# USBtoEthnet.net
KiCad netlist of a schematic drawn in Altium Designer
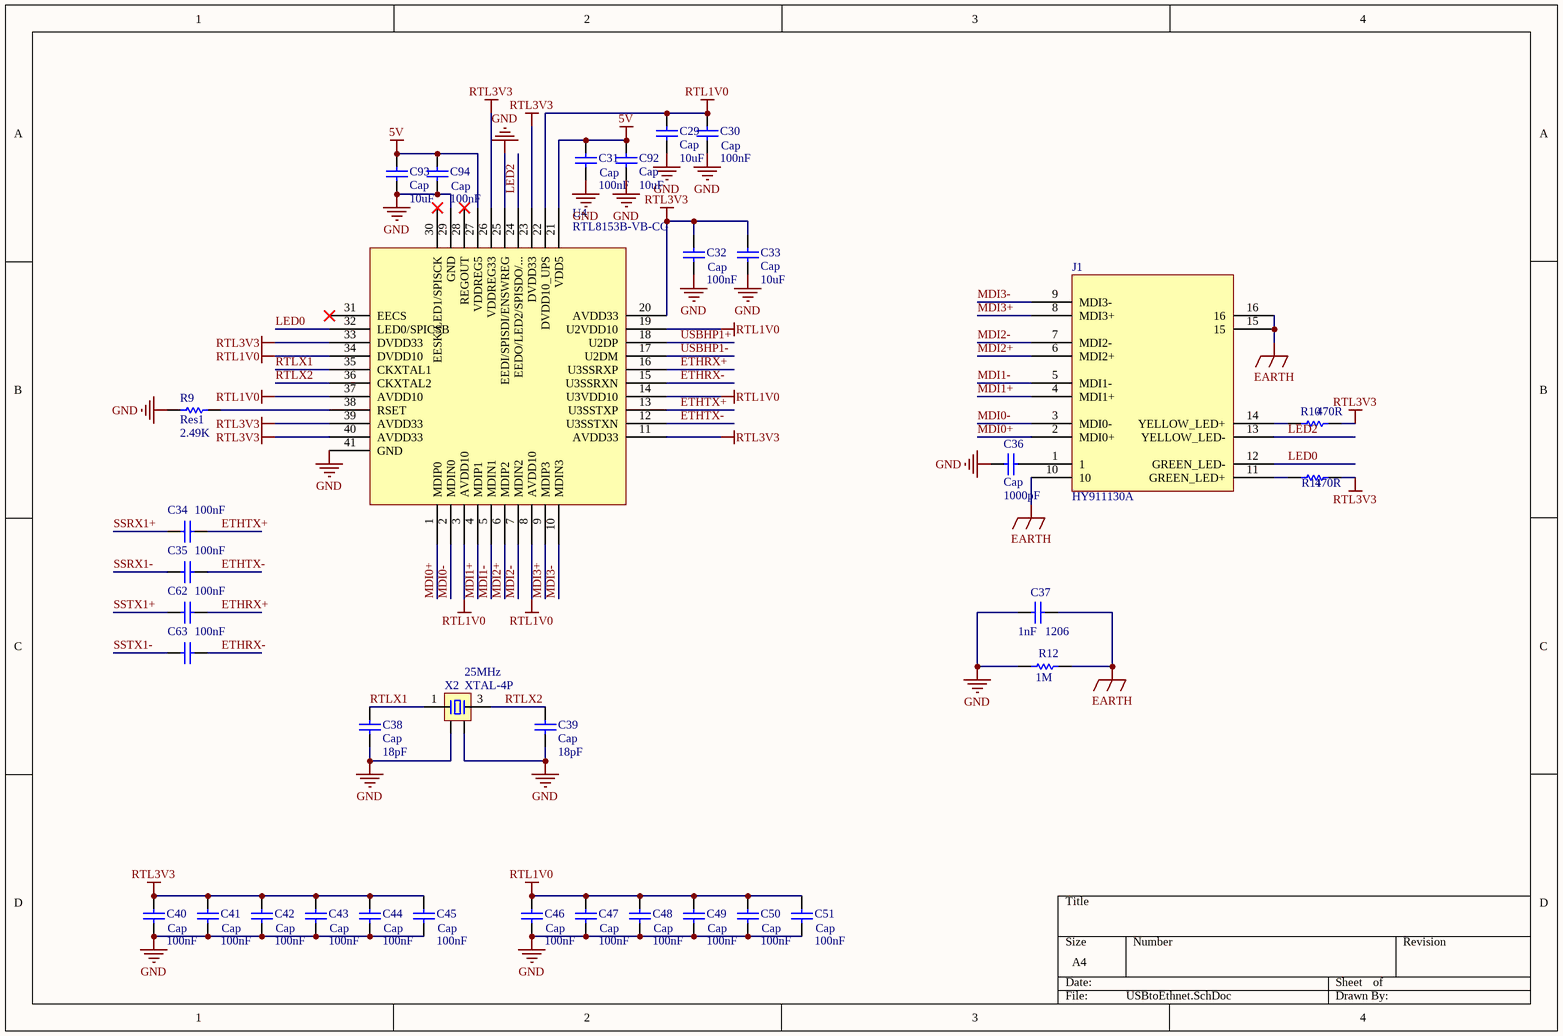
[diagram p0: USBtoEthnet.SchDoc]

(export (version "E")
  (design (tool "Eeschema 10.0.6"))
  (components
    (comp (ref "C29")
      (value "Cap")
      (footprint "C0603_M")
      (description "Capacitor")
      (fields (field (name "ALTIUM_VALUE") "10uF") (field (name "PUBLISHER") "Altium Limited"))
      (libsource (lib "Miscellaneous Devices") (part "Cap"))
    )
    (comp (ref "C30")
      (value "Cap")
      (footprint "C0603_M")
      (description "Capacitor")
      (fields (field (name "ALTIUM_VALUE") "100nF") (field (name "PUBLISHER") "Altium Limited"))
      (libsource (lib "Miscellaneous Devices") (part "Cap"))
    )
    (comp (ref "C31")
      (value "Cap")
      (footprint "C0603_M")
      (description "Capacitor")
      (fields (field (name "ALTIUM_VALUE") "100nF") (field (name "PUBLISHER") "Altium Limited"))
      (libsource (lib "Miscellaneous Devices") (part "Cap"))
    )
    (comp (ref "C32")
      (value "Cap")
      (footprint "C0603_M")
      (description "Capacitor")
      (fields (field (name "ALTIUM_VALUE") "100nF") (field (name "PUBLISHER") "Altium Limited"))
      (libsource (lib "Miscellaneous Devices") (part "Cap"))
    )
    (comp (ref "C33")
      (value "Cap")
      (footprint "C0603_M")
      (description "Capacitor")
      (fields (field (name "ALTIUM_VALUE") "10uF") (field (name "PUBLISHER") "Altium Limited"))
      (libsource (lib "Miscellaneous Devices") (part "Cap"))
    )
    (comp (ref "C34")
      (value "100nF")
      (footprint "1.03-电容:C0402_M")
      (description "Capacitor")
      (fields (field (name "Comment") "Cap") (field (name "PUBLISHER") "Altium Limited"))
      (libsource (lib "Miscellaneous Devices") (part "Cap"))
    )
    (comp (ref "C35")
      (value "100nF")
      (footprint "1.03-电容:C0402_M")
      (description "Capacitor")
      (fields (field (name "Comment") "Cap") (field (name "PUBLISHER") "Altium Limited"))
      (libsource (lib "Miscellaneous Devices") (part "Cap"))
    )
    (comp (ref "C36")
      (value "Cap")
      (footprint "1.03-电容:C0603_M")
      (description "Capacitor")
      (fields (field (name "ALTIUM_VALUE") "1000pF") (field (name "PUBLISHER") "Altium Limited"))
      (libsource (lib "Miscellaneous Devices") (part "Cap"))
    )
    (comp (ref "C37")
      (value "1nF")
      (footprint "1206")
      (description "Capacitor")
      (fields (field (name "Comment") "Cap") (field (name "PUBLISHER") "Altium Limited"))
      (libsource (lib "Miscellaneous Devices") (part "Cap"))
    )
    (comp (ref "C38")
      (value "Cap")
      (footprint "C0603_M")
      (description "Capacitor")
      (fields (field (name "ALTIUM_VALUE") "18pF") (field (name "PUBLISHER") "Altium Limited"))
      (libsource (lib "Miscellaneous Devices") (part "Cap"))
    )
    (comp (ref "C39")
      (value "Cap")
      (footprint "C0603_M")
      (description "Capacitor")
      (fields (field (name "ALTIUM_VALUE") "18pF") (field (name "PUBLISHER") "Altium Limited"))
      (libsource (lib "Miscellaneous Devices") (part "Cap"))
    )
    (comp (ref "C40")
      (value "Cap")
      (footprint "C0603_M")
      (description "Capacitor")
      (fields (field (name "ALTIUM_VALUE") "100nF") (field (name "PUBLISHER") "Altium Limited"))
      (libsource (lib "Miscellaneous Devices") (part "Cap"))
    )
    (comp (ref "C41")
      (value "Cap")
      (footprint "C0603_M")
      (description "Capacitor")
      (fields (field (name "ALTIUM_VALUE") "100nF") (field (name "PUBLISHER") "Altium Limited"))
      (libsource (lib "Miscellaneous Devices") (part "Cap"))
    )
    (comp (ref "C42")
      (value "Cap")
      (footprint "C0603_M")
      (description "Capacitor")
      (fields (field (name "ALTIUM_VALUE") "100nF") (field (name "PUBLISHER") "Altium Limited"))
      (libsource (lib "Miscellaneous Devices") (part "Cap"))
    )
    (comp (ref "C43")
      (value "Cap")
      (footprint "C0603_M")
      (description "Capacitor")
      (fields (field (name "ALTIUM_VALUE") "100nF") (field (name "PUBLISHER") "Altium Limited"))
      (libsource (lib "Miscellaneous Devices") (part "Cap"))
    )
    (comp (ref "C44")
      (value "Cap")
      (footprint "C0603_M")
      (description "Capacitor")
      (fields (field (name "ALTIUM_VALUE") "100nF") (field (name "PUBLISHER") "Altium Limited"))
      (libsource (lib "Miscellaneous Devices") (part "Cap"))
    )
    (comp (ref "C45")
      (value "Cap")
      (footprint "C0603_M")
      (description "Capacitor")
      (fields (field (name "ALTIUM_VALUE") "100nF") (field (name "PUBLISHER") "Altium Limited"))
      (libsource (lib "Miscellaneous Devices") (part "Cap"))
    )
    (comp (ref "C46")
      (value "Cap")
      (footprint "C0603_M")
      (description "Capacitor")
      (fields (field (name "ALTIUM_VALUE") "100nF") (field (name "PUBLISHER") "Altium Limited"))
      (libsource (lib "Miscellaneous Devices") (part "Cap"))
    )
    (comp (ref "C47")
      (value "Cap")
      (footprint "C0603_M")
      (description "Capacitor")
      (fields (field (name "ALTIUM_VALUE") "100nF") (field (name "PUBLISHER") "Altium Limited"))
      (libsource (lib "Miscellaneous Devices") (part "Cap"))
    )
    (comp (ref "C48")
      (value "Cap")
      (footprint "C0603_M")
      (description "Capacitor")
      (fields (field (name "ALTIUM_VALUE") "100nF") (field (name "PUBLISHER") "Altium Limited"))
      (libsource (lib "Miscellaneous Devices") (part "Cap"))
    )
    (comp (ref "C49")
      (value "Cap")
      (footprint "C0603_M")
      (description "Capacitor")
      (fields (field (name "ALTIUM_VALUE") "100nF") (field (name "PUBLISHER") "Altium Limited"))
      (libsource (lib "Miscellaneous Devices") (part "Cap"))
    )
    (comp (ref "C50")
      (value "Cap")
      (footprint "C0603_M")
      (description "Capacitor")
      (fields (field (name "ALTIUM_VALUE") "100nF") (field (name "PUBLISHER") "Altium Limited"))
      (libsource (lib "Miscellaneous Devices") (part "Cap"))
    )
    (comp (ref "C51")
      (value "Cap")
      (footprint "C0603_M")
      (description "Capacitor")
      (fields (field (name "ALTIUM_VALUE") "100nF") (field (name "PUBLISHER") "Altium Limited"))
      (libsource (lib "Miscellaneous Devices") (part "Cap"))
    )
    (comp (ref "C62")
      (value "100nF")
      (footprint "1.03-电容:C0402_M")
      (description "Capacitor")
      (fields (field (name "Comment") "Cap") (field (name "PUBLISHER") "Altium Limited"))
      (libsource (lib "Miscellaneous Devices") (part "Cap"))
    )
    (comp (ref "C63")
      (value "100nF")
      (footprint "1.03-电容:C0402_M")
      (description "Capacitor")
      (fields (field (name "Comment") "Cap") (field (name "PUBLISHER") "Altium Limited"))
      (libsource (lib "Miscellaneous Devices") (part "Cap"))
    )
    (comp (ref "C92")
      (value "Cap")
      (footprint "C0603_M")
      (description "Capacitor")
      (fields (field (name "ALTIUM_VALUE") "10uF") (field (name "PUBLISHER") "Altium Limited"))
      (libsource (lib "Miscellaneous Devices") (part "Cap"))
    )
    (comp (ref "C93")
      (value "Cap")
      (footprint "C0603_M")
      (description "Capacitor")
      (fields (field (name "ALTIUM_VALUE") "10uF") (field (name "PUBLISHER") "Altium Limited"))
      (libsource (lib "Miscellaneous Devices") (part "Cap"))
    )
    (comp (ref "C94")
      (value "Cap")
      (footprint "C0603_M")
      (description "Capacitor")
      (fields (field (name "ALTIUM_VALUE") "100nF") (field (name "PUBLISHER") "Altium Limited"))
      (libsource (lib "Miscellaneous Devices") (part "Cap"))
    )
    (comp (ref "J1")
      (value "HY911130A")
      (footprint "RJ45-TH_10P-P2.54-S2.54_L16.1-W21.4")
      (libsource (lib "MyIntLib") (part "HY911130A"))
    )
    (comp (ref "R9")
      (value "Res1")
      (footprint "R0603_M")
      (description "Resistor")
      (fields (field (name "ALTIUM_VALUE") "2.49K") (field (name "PUBLISHER") "Altium Limited"))
      (libsource (lib "Miscellaneous Devices") (part "Res1"))
    )
    (comp (ref "R10")
      (value "470R")
      (footprint "R0603_M")
      (description "Resistor")
      (fields (field (name "Comment") "Res1") (field (name "PUBLISHER") "Altium Limited"))
      (libsource (lib "Miscellaneous Devices") (part "Res1"))
    )
    (comp (ref "R11")
      (value "470R")
      (footprint "R0603_M")
      (description "Resistor")
      (fields (field (name "Comment") "Res1") (field (name "PUBLISHER") "Altium Limited"))
      (libsource (lib "Miscellaneous Devices") (part "Res1"))
    )
    (comp (ref "R12")
      (value "1M")
      (footprint "R0603_M")
      (description "Resistor")
      (fields (field (name "Comment") "Res1") (field (name "PUBLISHER") "Altium Limited"))
      (libsource (lib "Miscellaneous Devices") (part "Res1"))
    )
    (comp (ref "U4")
      (value "RTL8153B-VB-CG")
      (footprint "2.04-QFN-UFQFPN-VFQFPN封装:QFN40-L5.0-W5.0-P0.4")
      (libsource (lib "MyIntLib") (part "RTL8153B-VB-CG"))
    )
    (comp (ref "X2")
      (value "XTAL-4P")
      (footprint "OSC 3225-4P")
      (description "4脚无源晶振")
      (fields (field (name "PARAMETER 1") "25MHz"))
      (libsource (lib "晶振") (part "XTAL-4P"))
    )
  )
  (nets
    (net (code "1") (name "/ETHRX+") (class "Default")
      (node (ref "C62") (pin "1") (pinfunction "1_1") (pintype "passive"))
      (node (ref "U4") (pin "16") (pinfunction "U3SSRXP_16") (pintype "passive"))
    )
    (net (code "2") (name "/ETHRX-") (class "Default")
      (node (ref "C63") (pin "1") (pinfunction "1_1") (pintype "passive"))
      (node (ref "U4") (pin "15") (pinfunction "U3SSRXN_15") (pintype "passive"))
    )
    (net (code "3") (name "/ETHTX+") (class "Default")
      (node (ref "C34") (pin "1") (pinfunction "1_1") (pintype "passive"))
      (node (ref "U4") (pin "13") (pinfunction "U3SSTXP_13") (pintype "passive"))
    )
    (net (code "4") (name "/ETHTX-") (class "Default")
      (node (ref "C35") (pin "1") (pinfunction "1_1") (pintype "passive"))
      (node (ref "U4") (pin "12") (pinfunction "U3SSTXN_12") (pintype "passive"))
    )
    (net (code "5") (name "/LED0") (class "Default")
      (node (ref "J1") (pin "12") (pinfunction "GREEN_LED-_12") (pintype "passive"))
      (node (ref "U4") (pin "32") (pinfunction "LED0/SPICSB_32") (pintype "passive"))
    )
    (net (code "6") (name "/LED2") (class "Default")
      (node (ref "J1") (pin "13") (pinfunction "YELLOW_LED-_13") (pintype "passive"))
      (node (ref "U4") (pin "24") (pinfunction "EEDO/LED2/SPISDO/..._24") (pintype "passive"))
    )
    (net (code "7") (name "/MDI0+") (class "Default")
      (node (ref "J1") (pin "2") (pinfunction "MDI0+_2") (pintype "passive"))
      (node (ref "U4") (pin "1") (pinfunction "MDIP0_1") (pintype "passive"))
    )
    (net (code "8") (name "/MDI0-") (class "Default")
      (node (ref "J1") (pin "3") (pinfunction "MDI0-_3") (pintype "passive"))
      (node (ref "U4") (pin "2") (pinfunction "MDIN0_2") (pintype "passive"))
    )
    (net (code "9") (name "/MDI1+") (class "Default")
      (node (ref "J1") (pin "4") (pinfunction "MDI1+_4") (pintype "passive"))
      (node (ref "U4") (pin "4") (pinfunction "MDIP1_4") (pintype "passive"))
    )
    (net (code "10") (name "/MDI1-") (class "Default")
      (node (ref "J1") (pin "5") (pinfunction "MDI1-_5") (pintype "passive"))
      (node (ref "U4") (pin "5") (pinfunction "MDIN1_5") (pintype "passive"))
    )
    (net (code "11") (name "/MDI2+") (class "Default")
      (node (ref "J1") (pin "6") (pinfunction "MDI2+_6") (pintype "passive"))
      (node (ref "U4") (pin "6") (pinfunction "MDIP2_6") (pintype "passive"))
    )
    (net (code "12") (name "/MDI2-") (class "Default")
      (node (ref "J1") (pin "7") (pinfunction "MDI2-_7") (pintype "passive"))
      (node (ref "U4") (pin "7") (pinfunction "MDIN2_7") (pintype "passive"))
    )
    (net (code "13") (name "/MDI3+") (class "Default")
      (node (ref "J1") (pin "8") (pinfunction "MDI3+_8") (pintype "passive"))
      (node (ref "U4") (pin "9") (pinfunction "MDIP3_9") (pintype "passive"))
    )
    (net (code "14") (name "/MDI3-") (class "Default")
      (node (ref "J1") (pin "9") (pinfunction "MDI3-_9") (pintype "passive"))
      (node (ref "U4") (pin "10") (pinfunction "MDIN3_10") (pintype "passive"))
    )
    (net (code "15") (name "/RTLX1") (class "Default")
      (node (ref "C38") (pin "1") (pinfunction "1_1") (pintype "passive"))
      (node (ref "U4") (pin "35") (pinfunction "CKXTAL1_35") (pintype "passive"))
      (node (ref "X2") (pin "1") (pinfunction "1_1") (pintype "passive"))
    )
    (net (code "16") (name "/RTLX2") (class "Default")
      (node (ref "C39") (pin "1") (pinfunction "1_1") (pintype "passive"))
      (node (ref "U4") (pin "36") (pinfunction "CKXTAL2_36") (pintype "passive"))
      (node (ref "X2") (pin "3") (pinfunction "3_3") (pintype "passive"))
    )
    (net (code "17") (name "/SSRX1+") (class "Default")
      (node (ref "C34") (pin "2") (pinfunction "2_2") (pintype "passive"))
    )
    (net (code "18") (name "/SSRX1-") (class "Default")
      (node (ref "C35") (pin "2") (pinfunction "2_2") (pintype "passive"))
    )
    (net (code "19") (name "/SSTX1+") (class "Default")
      (node (ref "C62") (pin "2") (pinfunction "2_2") (pintype "passive"))
    )
    (net (code "20") (name "/SSTX1-") (class "Default")
      (node (ref "C63") (pin "2") (pinfunction "2_2") (pintype "passive"))
    )
    (net (code "21") (name "/USBHP1+") (class "Default")
      (node (ref "U4") (pin "18") (pinfunction "U2DP_18") (pintype "passive"))
    )
    (net (code "22") (name "/USBHP1-") (class "Default")
      (node (ref "U4") (pin "17") (pinfunction "U2DM_17") (pintype "passive"))
    )
    (net (code "23") (name "5V") (class "Default")
      (node (ref "C31") (pin "1") (pinfunction "1_1") (pintype "passive"))
      (node (ref "C92") (pin "1") (pinfunction "1_1") (pintype "passive"))
      (node (ref "C93") (pin "1") (pinfunction "1_1") (pintype "passive"))
      (node (ref "C94") (pin "1") (pinfunction "1_1") (pintype "passive"))
      (node (ref "U4") (pin "21") (pinfunction "VDD5_21") (pintype "passive"))
      (node (ref "U4") (pin "27") (pinfunction "VDDREG5_27") (pintype "passive"))
    )
    (net (code "24") (name "EARTH") (class "Default")
      (node (ref "C37") (pin "2") (pinfunction "2_2") (pintype "passive"))
      (node (ref "J1") (pin "10") (pinfunction "10_10") (pintype "passive"))
      (node (ref "J1") (pin "15") (pinfunction "15_15") (pintype "passive"))
      (node (ref "J1") (pin "16") (pinfunction "16_16") (pintype "passive"))
      (node (ref "R12") (pin "1") (pinfunction "1_1") (pintype "passive"))
    )
    (net (code "25") (name "GND") (class "Default")
      (node (ref "C29") (pin "2") (pinfunction "2_2") (pintype "passive"))
      (node (ref "C30") (pin "2") (pinfunction "2_2") (pintype "passive"))
      (node (ref "C31") (pin "2") (pinfunction "2_2") (pintype "passive"))
      (node (ref "C32") (pin "2") (pinfunction "2_2") (pintype "passive"))
      (node (ref "C33") (pin "2") (pinfunction "2_2") (pintype "passive"))
      (node (ref "C36") (pin "1") (pinfunction "1_1") (pintype "passive"))
      (node (ref "C37") (pin "1") (pinfunction "1_1") (pintype "passive"))
      (node (ref "C38") (pin "2") (pinfunction "2_2") (pintype "passive"))
      (node (ref "C39") (pin "2") (pinfunction "2_2") (pintype "passive"))
      (node (ref "C40") (pin "2") (pinfunction "2_2") (pintype "passive"))
      (node (ref "C41") (pin "2") (pinfunction "2_2") (pintype "passive"))
      (node (ref "C42") (pin "2") (pinfunction "2_2") (pintype "passive"))
      (node (ref "C43") (pin "2") (pinfunction "2_2") (pintype "passive"))
      (node (ref "C44") (pin "2") (pinfunction "2_2") (pintype "passive"))
      (node (ref "C45") (pin "2") (pinfunction "2_2") (pintype "passive"))
      (node (ref "C46") (pin "2") (pinfunction "2_2") (pintype "passive"))
      (node (ref "C47") (pin "2") (pinfunction "2_2") (pintype "passive"))
      (node (ref "C48") (pin "2") (pinfunction "2_2") (pintype "passive"))
      (node (ref "C49") (pin "2") (pinfunction "2_2") (pintype "passive"))
      (node (ref "C50") (pin "2") (pinfunction "2_2") (pintype "passive"))
      (node (ref "C51") (pin "2") (pinfunction "2_2") (pintype "passive"))
      (node (ref "C92") (pin "2") (pinfunction "2_2") (pintype "passive"))
      (node (ref "C93") (pin "2") (pinfunction "2_2") (pintype "passive"))
      (node (ref "C94") (pin "2") (pinfunction "2_2") (pintype "passive"))
      (node (ref "R12") (pin "2") (pinfunction "2_2") (pintype "passive"))
      (node (ref "R9") (pin "1") (pinfunction "1_1") (pintype "passive"))
      (node (ref "U4") (pin "25") (pinfunction "EEDI/SPISDI/ENSWREG_25") (pintype "passive"))
      (node (ref "U4") (pin "29") (pinfunction "GND_29") (pintype "passive"))
      (node (ref "U4") (pin "41") (pinfunction "GND_41") (pintype "passive"))
      (node (ref "X2") (pin "2") (pinfunction "2_2") (pintype "passive"))
      (node (ref "X2") (pin "4") (pinfunction "4_4") (pintype "passive"))
    )
    (net (code "26") (name "Net-(C36-Pad2)") (class "Default")
      (node (ref "C36") (pin "2") (pinfunction "2_2") (pintype "passive"))
      (node (ref "J1") (pin "1") (pinfunction "1_1") (pintype "passive"))
    )
    (net (code "27") (name "Net-(J1-GREEN_LED+)") (class "Default")
      (node (ref "J1") (pin "11") (pinfunction "GREEN_LED+_11") (pintype "passive"))
      (node (ref "R11") (pin "2") (pinfunction "2_2") (pintype "passive"))
    )
    (net (code "28") (name "Net-(J1-YELLOW_LED+)") (class "Default")
      (node (ref "J1") (pin "14") (pinfunction "YELLOW_LED+_14") (pintype "passive"))
      (node (ref "R10") (pin "1") (pinfunction "1_1") (pintype "passive"))
    )
    (net (code "29") (name "Net-(U4-RSET)") (class "Default")
      (node (ref "R9") (pin "2") (pinfunction "2_2") (pintype "passive"))
      (node (ref "U4") (pin "38") (pinfunction "RSET_38") (pintype "passive"))
    )
    (net (code "30") (name "RTL1V0") (class "Default")
      (node (ref "C29") (pin "1") (pinfunction "1_1") (pintype "passive"))
      (node (ref "C30") (pin "1") (pinfunction "1_1") (pintype "passive"))
      (node (ref "C46") (pin "1") (pinfunction "1_1") (pintype "passive"))
      (node (ref "C47") (pin "1") (pinfunction "1_1") (pintype "passive"))
      (node (ref "C48") (pin "1") (pinfunction "1_1") (pintype "passive"))
      (node (ref "C49") (pin "1") (pinfunction "1_1") (pintype "passive"))
      (node (ref "C50") (pin "1") (pinfunction "1_1") (pintype "passive"))
      (node (ref "C51") (pin "1") (pinfunction "1_1") (pintype "passive"))
      (node (ref "U4") (pin "14") (pinfunction "U3VDD10_14") (pintype "passive"))
      (node (ref "U4") (pin "19") (pinfunction "U2VDD10_19") (pintype "passive"))
      (node (ref "U4") (pin "22") (pinfunction "DVDD10_UPS_22") (pintype "passive"))
      (node (ref "U4") (pin "3") (pinfunction "AVDD10_3") (pintype "passive"))
      (node (ref "U4") (pin "34") (pinfunction "DVDD10_34") (pintype "passive"))
      (node (ref "U4") (pin "37") (pinfunction "AVDD10_37") (pintype "passive"))
      (node (ref "U4") (pin "8") (pinfunction "AVDD10_8") (pintype "passive"))
    )
    (net (code "31") (name "RTL3V3") (class "Default")
      (node (ref "C32") (pin "1") (pinfunction "1_1") (pintype "passive"))
      (node (ref "C33") (pin "1") (pinfunction "1_1") (pintype "passive"))
      (node (ref "C40") (pin "1") (pinfunction "1_1") (pintype "passive"))
      (node (ref "C41") (pin "1") (pinfunction "1_1") (pintype "passive"))
      (node (ref "C42") (pin "1") (pinfunction "1_1") (pintype "passive"))
      (node (ref "C43") (pin "1") (pinfunction "1_1") (pintype "passive"))
      (node (ref "C44") (pin "1") (pinfunction "1_1") (pintype "passive"))
      (node (ref "C45") (pin "1") (pinfunction "1_1") (pintype "passive"))
      (node (ref "R10") (pin "2") (pinfunction "2_2") (pintype "passive"))
      (node (ref "R11") (pin "1") (pinfunction "1_1") (pintype "passive"))
      (node (ref "U4") (pin "11") (pinfunction "AVDD33_11") (pintype "passive"))
      (node (ref "U4") (pin "20") (pinfunction "AVDD33_20") (pintype "passive"))
      (node (ref "U4") (pin "23") (pinfunction "DVDD33_23") (pintype "passive"))
      (node (ref "U4") (pin "26") (pinfunction "VDDREG33_26") (pintype "passive"))
      (node (ref "U4") (pin "33") (pinfunction "DVDD33_33") (pintype "passive"))
      (node (ref "U4") (pin "39") (pinfunction "AVDD33_39") (pintype "passive"))
      (node (ref "U4") (pin "40") (pinfunction "AVDD33_40") (pintype "passive"))
    )
    (net (code "32") (name "unconnected-(U4-EECS-Pad31)") (class "Default")
      (node (ref "U4") (pin "31") (pinfunction "EECS_31") (pintype "passive+no_connect"))
    )
    (net (code "33") (name "unconnected-(U4-EESK{slash}LED1{slash}SPISCK-Pad30)") (class "Default")
      (node (ref "U4") (pin "30") (pinfunction "EESK/LED1/SPISCK_30") (pintype "passive+no_connect"))
    )
    (net (code "34") (name "unconnected-(U4-REGOUT-Pad28)") (class "Default")
      (node (ref "U4") (pin "28") (pinfunction "REGOUT_28") (pintype "passive+no_connect"))
    )
  )
)
